# Power.net
KiCad netlist of a schematic drawn in Altium Designer
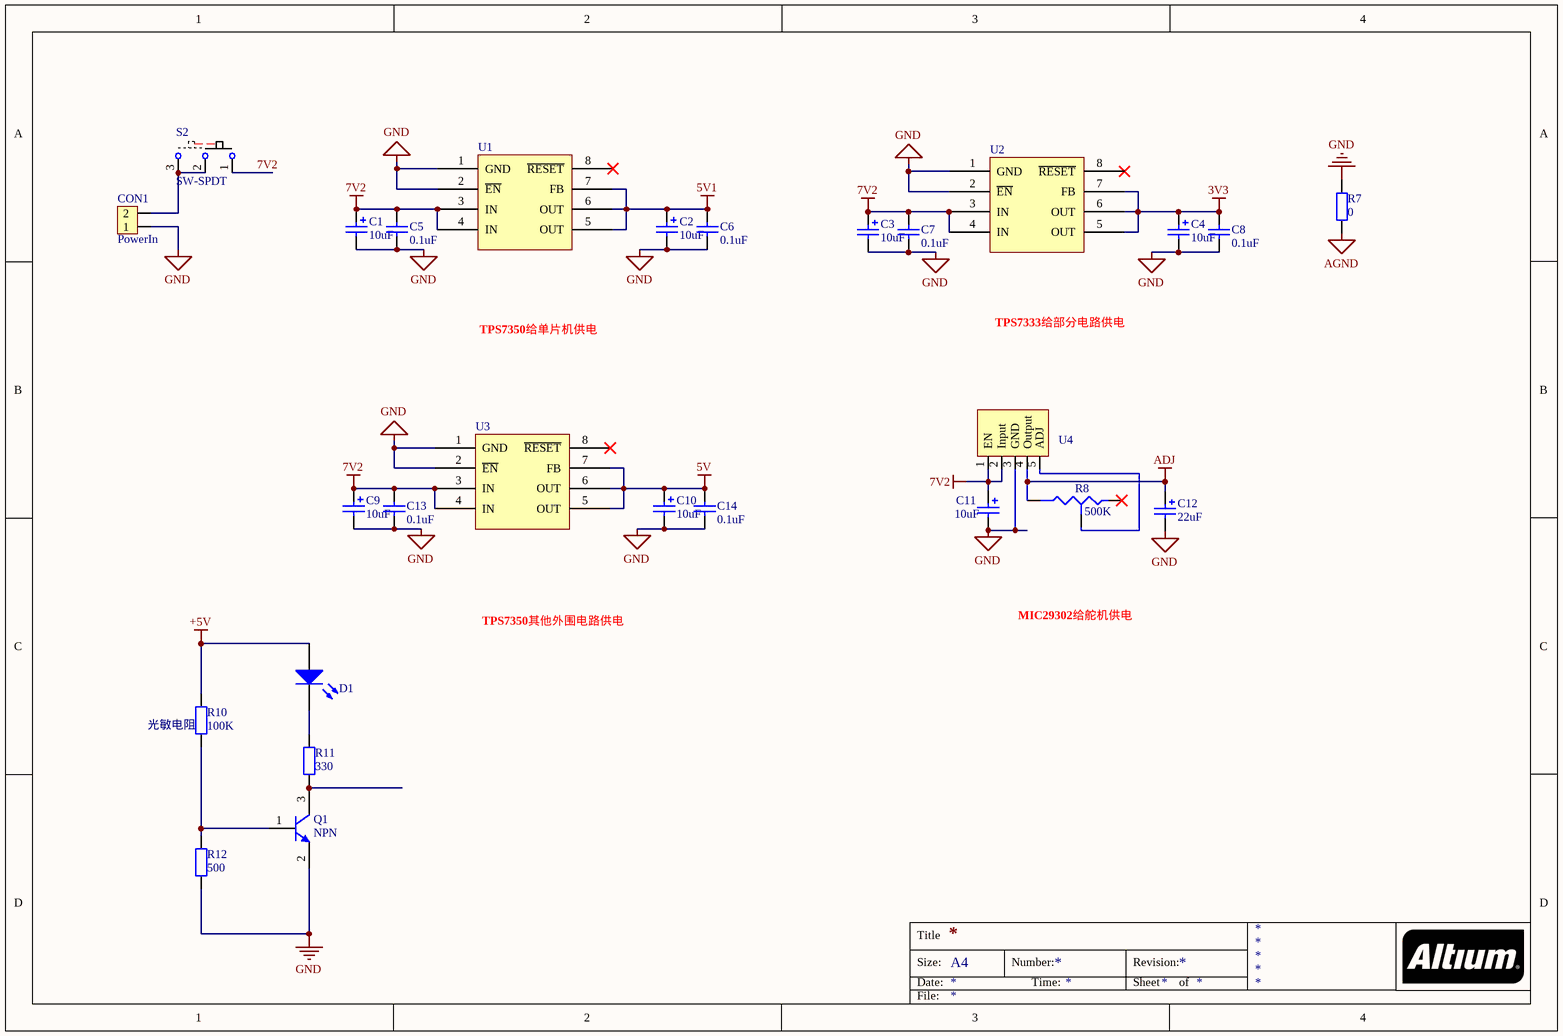
[diagram p0: Power.SchDoc]

(export (version "E")
  (design (tool "Eeschema 10.0.6"))
  (components
    (comp (ref "C1")
      (value "10uF")
      (footprint "Cap-Pol-10UF")
      (description "Polarized Capacitor (Surface Mount)")
      (fields (field (name "Comment") "Cap Pol_22uF") (field (name "PUBLISHER") "Altium Limited"))
      (libsource (lib "My") (part "Cap Pol_22uF"))
    )
    (comp (ref "C2")
      (value "10uF")
      (footprint "Cap-Pol-10UF")
      (description "Polarized Capacitor (Surface Mount)")
      (fields (field (name "Comment") "Cap Pol_22uF") (field (name "PUBLISHER") "Altium Limited"))
      (libsource (lib "My") (part "Cap Pol_22uF"))
    )
    (comp (ref "C3")
      (value "10uF")
      (footprint "Cap-Pol-10UF")
      (description "Polarized Capacitor (Surface Mount)")
      (fields (field (name "Comment") "Cap Pol_22uF") (field (name "PUBLISHER") "Altium Limited"))
      (libsource (lib "My") (part "Cap Pol_22uF"))
    )
    (comp (ref "C4")
      (value "10uF")
      (footprint "Cap-Pol-10UF")
      (description "Polarized Capacitor (Surface Mount)")
      (fields (field (name "Comment") "Cap Pol_22uF") (field (name "PUBLISHER") "Altium Limited"))
      (libsource (lib "My") (part "Cap Pol_22uF"))
    )
    (comp (ref "C5")
      (value "0.1uF")
      (footprint "Cap-0805C")
      (description "Capacitor (Semiconductor SIM Model)")
      (fields (field (name "Comment") "Cap Semi") (field (name "PUBLISHER") "Altium Limited"))
      (libsource (lib "My") (part "Cap Semi"))
    )
    (comp (ref "C6")
      (value "0.1uF")
      (footprint "Cap-0805C")
      (description "Capacitor (Semiconductor SIM Model)")
      (fields (field (name "Comment") "Cap Semi") (field (name "PUBLISHER") "Altium Limited"))
      (libsource (lib "My") (part "Cap Semi"))
    )
    (comp (ref "C7")
      (value "0.1uF")
      (footprint "Cap-0805C")
      (description "Capacitor (Semiconductor SIM Model)")
      (fields (field (name "Comment") "Cap Semi") (field (name "PUBLISHER") "Altium Limited"))
      (libsource (lib "My") (part "Cap Semi"))
    )
    (comp (ref "C8")
      (value "0.1uF")
      (footprint "Cap-0805C")
      (description "Capacitor (Semiconductor SIM Model)")
      (fields (field (name "Comment") "Cap Semi") (field (name "PUBLISHER") "Altium Limited"))
      (libsource (lib "My") (part "Cap Semi"))
    )
    (comp (ref "C9")
      (value "10uF")
      (footprint "Cap-Pol-10UF")
      (description "Polarized Capacitor (Surface Mount)")
      (fields (field (name "Comment") "Cap Pol_22uF") (field (name "PUBLISHER") "Altium Limited"))
      (libsource (lib "My") (part "Cap Pol_22uF"))
    )
    (comp (ref "C10")
      (value "10uF")
      (footprint "Cap-Pol-10UF")
      (description "Polarized Capacitor (Surface Mount)")
      (fields (field (name "Comment") "Cap Pol_22uF") (field (name "PUBLISHER") "Altium Limited"))
      (libsource (lib "My") (part "Cap Pol_22uF"))
    )
    (comp (ref "C11")
      (value "10uF")
      (footprint "Cap-Pol-10UF")
      (description "Polarized Capacitor (Surface Mount)")
      (fields (field (name "Comment") "Cap Pol") (field (name "PUBLISHER") "Altium Limited"))
      (libsource (lib "My") (part "Cap Pol"))
    )
    (comp (ref "C12")
      (value "22uF")
      (footprint "Cap-Pol-10UF")
      (description "Polarized Capacitor (Surface Mount)")
      (fields (field (name "Comment") "Cap Pol_22uF") (field (name "PUBLISHER") "Altium Limited"))
      (libsource (lib "My") (part "Cap Pol_22uF"))
    )
    (comp (ref "C13")
      (value "0.1uF")
      (footprint "Cap-0805C")
      (description "Capacitor (Semiconductor SIM Model)")
      (fields (field (name "Comment") "Cap Semi") (field (name "PUBLISHER") "Altium Limited"))
      (libsource (lib "My") (part "Cap Semi"))
    )
    (comp (ref "C14")
      (value "0.1uF")
      (footprint "Cap-0805C")
      (description "Capacitor (Semiconductor SIM Model)")
      (fields (field (name "Comment") "Cap Semi") (field (name "PUBLISHER") "Altium Limited"))
      (libsource (lib "My") (part "Cap Semi"))
    )
    (comp (ref "CON1")
      (value "PowerIn")
      (footprint "KF301-2P")
      (description "Header, 2-Pin")
      (libsource (lib "MOS motor driving module ") (part "Header 2"))
    )
    (comp (ref "D1")
      (value "LED0")
      (footprint "LED-0805")
      (description "发光二极管")
      (fields (field (name "PUBLISHER") "Altium Limited"))
      (libsource (lib "Fszhang") (part "LED0"))
    )
    (comp (ref "Q1")
      (value "NPN")
      (footprint "SOT23-3")
      (description "贴片三极管")
      (fields (field (name "PUBLISHER") "Altium Limited"))
      (libsource (lib "Fszhang") (part "NPN1"))
    )
    (comp (ref "R7")
      (value "0")
      (footprint "ty0805ss")
      (description "Resistor贴片封装")
      (fields (field (name "Comment") "Res2") (field (name "PUBLISHER") "Altium Limited"))
      (libsource (lib "") (part "Res2_1"))
    )
    (comp (ref "R8") (value "500K") (footprint "VR_3362P") (libsource (lib "1209Lab") (part "RES-ADJ")))
    (comp (ref "R10")
      (value "光敏电阻")
      (footprint "ty0805ss")
      (description "Resistor贴片封装")
      (fields (field (name "ALTIUM_VALUE") "100K") (field (name "PUBLISHER") "Altium Limited"))
      (libsource (lib "My") (part "Res2"))
    )
    (comp (ref "R11")
      (value "330")
      (footprint "ty0805ss")
      (description "Resistor贴片封装")
      (fields (field (name "Comment") "Res2") (field (name "PUBLISHER") "Altium Limited"))
      (libsource (lib "My") (part "Res2"))
    )
    (comp (ref "R12")
      (value "500")
      (footprint "ty0805ss")
      (description "Resistor贴片封装")
      (fields (field (name "Comment") "Res2") (field (name "PUBLISHER") "Altium Limited"))
      (libsource (lib "My") (part "Res2"))
    )
    (comp (ref "S2")
      (value "SW-SPDT")
      (footprint "SWICH_2")
      (description "SPDT Subminiature Toggle Switch, Right Angle Mounting, Vertical Actuation")
      (libsource (lib "MOS motor driving module ") (part "SW-SPDT"))
    )
    (comp (ref "U1") (value "TPS7350给单片机供电") (footprint "SO-8") (libsource (lib "My") (part "TPS7350")))
    (comp (ref "U2") (value "TPS7333给部分电路供电") (footprint "SO-8") (libsource (lib "My") (part "TPS7333")))
    (comp (ref "U3") (value "TPS7350其他外围电路供电") (footprint "SO-8") (libsource (lib "My") (part "TPS7350")))
    (comp (ref "U4")
      (value "MIC29302给舵机供电")
      (footprint "TO263-5")
      (libsource (lib "1209Lab") (part "MIC29032"))
    )
  )
  (nets
    (net (code "1") (name "+5V") (class "Default")
      (node (ref "D1") (pin "1") (pinfunction "A_1") (pintype "passive"))
      (node (ref "R10") (pin "1") (pinfunction "1_1") (pintype "passive"))
    )
    (net (code "2") (name "3V3") (class "Default")
      (node (ref "C4") (pin "1") (pinfunction "1_1") (pintype "passive"))
      (node (ref "C8") (pin "1") (pinfunction "1_1") (pintype "passive"))
      (node (ref "U2") (pin "5") (pinfunction "OUT_5") (pintype "passive"))
      (node (ref "U2") (pin "6") (pinfunction "OUT_6") (pintype "passive"))
      (node (ref "U2") (pin "7") (pinfunction "FB_7") (pintype "passive"))
    )
    (net (code "3") (name "5V") (class "Default")
      (node (ref "C10") (pin "1") (pinfunction "1_1") (pintype "passive"))
      (node (ref "C14") (pin "1") (pinfunction "1_1") (pintype "passive"))
      (node (ref "U3") (pin "5") (pinfunction "OUT_5") (pintype "passive"))
      (node (ref "U3") (pin "6") (pinfunction "OUT_6") (pintype "passive"))
      (node (ref "U3") (pin "7") (pinfunction "FB_7") (pintype "passive"))
    )
    (net (code "4") (name "5V1") (class "Default")
      (node (ref "C2") (pin "1") (pinfunction "1_1") (pintype "passive"))
      (node (ref "C6") (pin "1") (pinfunction "1_1") (pintype "passive"))
      (node (ref "U1") (pin "5") (pinfunction "OUT_5") (pintype "passive"))
      (node (ref "U1") (pin "6") (pinfunction "OUT_6") (pintype "passive"))
      (node (ref "U1") (pin "7") (pinfunction "FB_7") (pintype "passive"))
    )
    (net (code "5") (name "7V2") (class "Default")
      (node (ref "C1") (pin "1") (pinfunction "1_1") (pintype "passive"))
      (node (ref "C11") (pin "1") (pinfunction "1_1") (pintype "passive"))
      (node (ref "C13") (pin "1") (pinfunction "1_1") (pintype "passive"))
      (node (ref "C3") (pin "1") (pinfunction "1_1") (pintype "passive"))
      (node (ref "C5") (pin "1") (pinfunction "1_1") (pintype "passive"))
      (node (ref "C7") (pin "1") (pinfunction "1_1") (pintype "passive"))
      (node (ref "C9") (pin "1") (pinfunction "1_1") (pintype "passive"))
      (node (ref "S2") (pin "1") (pinfunction "1_1") (pintype "passive"))
      (node (ref "U1") (pin "3") (pinfunction "IN_3") (pintype "passive"))
      (node (ref "U1") (pin "4") (pinfunction "IN_4") (pintype "passive"))
      (node (ref "U2") (pin "3") (pinfunction "IN_3") (pintype "passive"))
      (node (ref "U2") (pin "4") (pinfunction "IN_4") (pintype "passive"))
      (node (ref "U3") (pin "3") (pinfunction "IN_3") (pintype "passive"))
      (node (ref "U3") (pin "4") (pinfunction "IN_4") (pintype "passive"))
      (node (ref "U4") (pin "1") (pinfunction "EN_1") (pintype "passive"))
      (node (ref "U4") (pin "2") (pinfunction "Input_2") (pintype "passive"))
    )
    (net (code "6") (name "ADJ") (class "Default")
      (node (ref "C12") (pin "1") (pinfunction "1_1") (pintype "passive"))
      (node (ref "R8") (pin "3") (pinfunction "3_3") (pintype "passive"))
      (node (ref "U4") (pin "4") (pinfunction "Output_4") (pintype "passive"))
    )
    (net (code "7") (name "AGND") (class "Default")
      (node (ref "R7") (pin "1") (pinfunction "1_1") (pintype "passive"))
    )
    (net (code "8") (name "GND") (class "Default")
      (node (ref "C1") (pin "2") (pinfunction "2_2") (pintype "passive"))
      (node (ref "C10") (pin "2") (pinfunction "2_2") (pintype "passive"))
      (node (ref "C11") (pin "2") (pinfunction "2_2") (pintype "passive"))
      (node (ref "C12") (pin "2") (pinfunction "2_2") (pintype "passive"))
      (node (ref "C13") (pin "2") (pinfunction "2_2") (pintype "passive"))
      (node (ref "C14") (pin "2") (pinfunction "2_2") (pintype "passive"))
      (node (ref "C2") (pin "2") (pinfunction "2_2") (pintype "passive"))
      (node (ref "C3") (pin "2") (pinfunction "2_2") (pintype "passive"))
      (node (ref "C4") (pin "2") (pinfunction "2_2") (pintype "passive"))
      (node (ref "C5") (pin "2") (pinfunction "2_2") (pintype "passive"))
      (node (ref "C6") (pin "2") (pinfunction "2_2") (pintype "passive"))
      (node (ref "C7") (pin "2") (pinfunction "2_2") (pintype "passive"))
      (node (ref "C8") (pin "2") (pinfunction "2_2") (pintype "passive"))
      (node (ref "C9") (pin "2") (pinfunction "2_2") (pintype "passive"))
      (node (ref "CON1") (pin "1") (pinfunction "1_1") (pintype "passive"))
      (node (ref "Q1") (pin "2") (pinfunction "E_2") (pintype "passive"))
      (node (ref "R12") (pin "2") (pinfunction "2_2") (pintype "passive"))
      (node (ref "R7") (pin "2") (pinfunction "2_2") (pintype "passive"))
      (node (ref "U1") (pin "1") (pinfunction "GND_1") (pintype "passive"))
      (node (ref "U1") (pin "2") (pinfunction "~{EN}_2") (pintype "passive"))
      (node (ref "U2") (pin "1") (pinfunction "GND_1") (pintype "passive"))
      (node (ref "U2") (pin "2") (pinfunction "~{EN}_2") (pintype "passive"))
      (node (ref "U3") (pin "1") (pinfunction "GND_1") (pintype "passive"))
      (node (ref "U3") (pin "2") (pinfunction "~{EN}_2") (pintype "passive"))
      (node (ref "U4") (pin "3") (pinfunction "GND_3") (pintype "passive"))
    )
    (net (code "9") (name "Net-(CON1-Pad2)") (class "Default")
      (node (ref "CON1") (pin "2") (pinfunction "2_2") (pintype "passive"))
      (node (ref "S2") (pin "2") (pinfunction "2_2") (pintype "passive"))
      (node (ref "S2") (pin "3") (pinfunction "3_3") (pintype "passive"))
    )
    (net (code "10") (name "Net-(D1-K)") (class "Default")
      (node (ref "D1") (pin "2") (pinfunction "K_2") (pintype "passive"))
      (node (ref "R11") (pin "1") (pinfunction "1_1") (pintype "passive"))
    )
    (net (code "11") (name "Net-(Q1-B)") (class "Default")
      (node (ref "Q1") (pin "1") (pinfunction "B_1") (pintype "passive"))
      (node (ref "R10") (pin "2") (pinfunction "2_2") (pintype "passive"))
      (node (ref "R12") (pin "1") (pinfunction "1_1") (pintype "passive"))
    )
    (net (code "12") (name "Net-(Q1-C)") (class "Default")
      (node (ref "Q1") (pin "3") (pinfunction "C_3") (pintype "passive"))
      (node (ref "R11") (pin "2") (pinfunction "2_2") (pintype "passive"))
    )
    (net (code "13") (name "Net-(U4-ADJ)") (class "Default")
      (node (ref "R8") (pin "2") (pinfunction "2_2") (pintype "passive"))
      (node (ref "U4") (pin "5") (pinfunction "ADJ_5") (pintype "passive"))
    )
    (net (code "14") (name "unconnected-(R8-Pad1)") (class "Default")
      (node (ref "R8") (pin "1") (pinfunction "1_1") (pintype "passive+no_connect"))
    )
    (net (code "15") (name "unconnected-(U1-~{RESET}-Pad8)") (class "Default")
      (node (ref "U1") (pin "8") (pinfunction "~{RESET}_8") (pintype "passive+no_connect"))
    )
    (net (code "16") (name "unconnected-(U2-~{RESET}-Pad8)") (class "Default")
      (node (ref "U2") (pin "8") (pinfunction "~{RESET}_8") (pintype "passive+no_connect"))
    )
    (net (code "17") (name "unconnected-(U3-~{RESET}-Pad8)") (class "Default")
      (node (ref "U3") (pin "8") (pinfunction "~{RESET}_8") (pintype "passive+no_connect"))
    )
  )
)
